# VarmoLed_-_Rev_A1.net
KiCad netlist of a schematic drawn in EAGLE
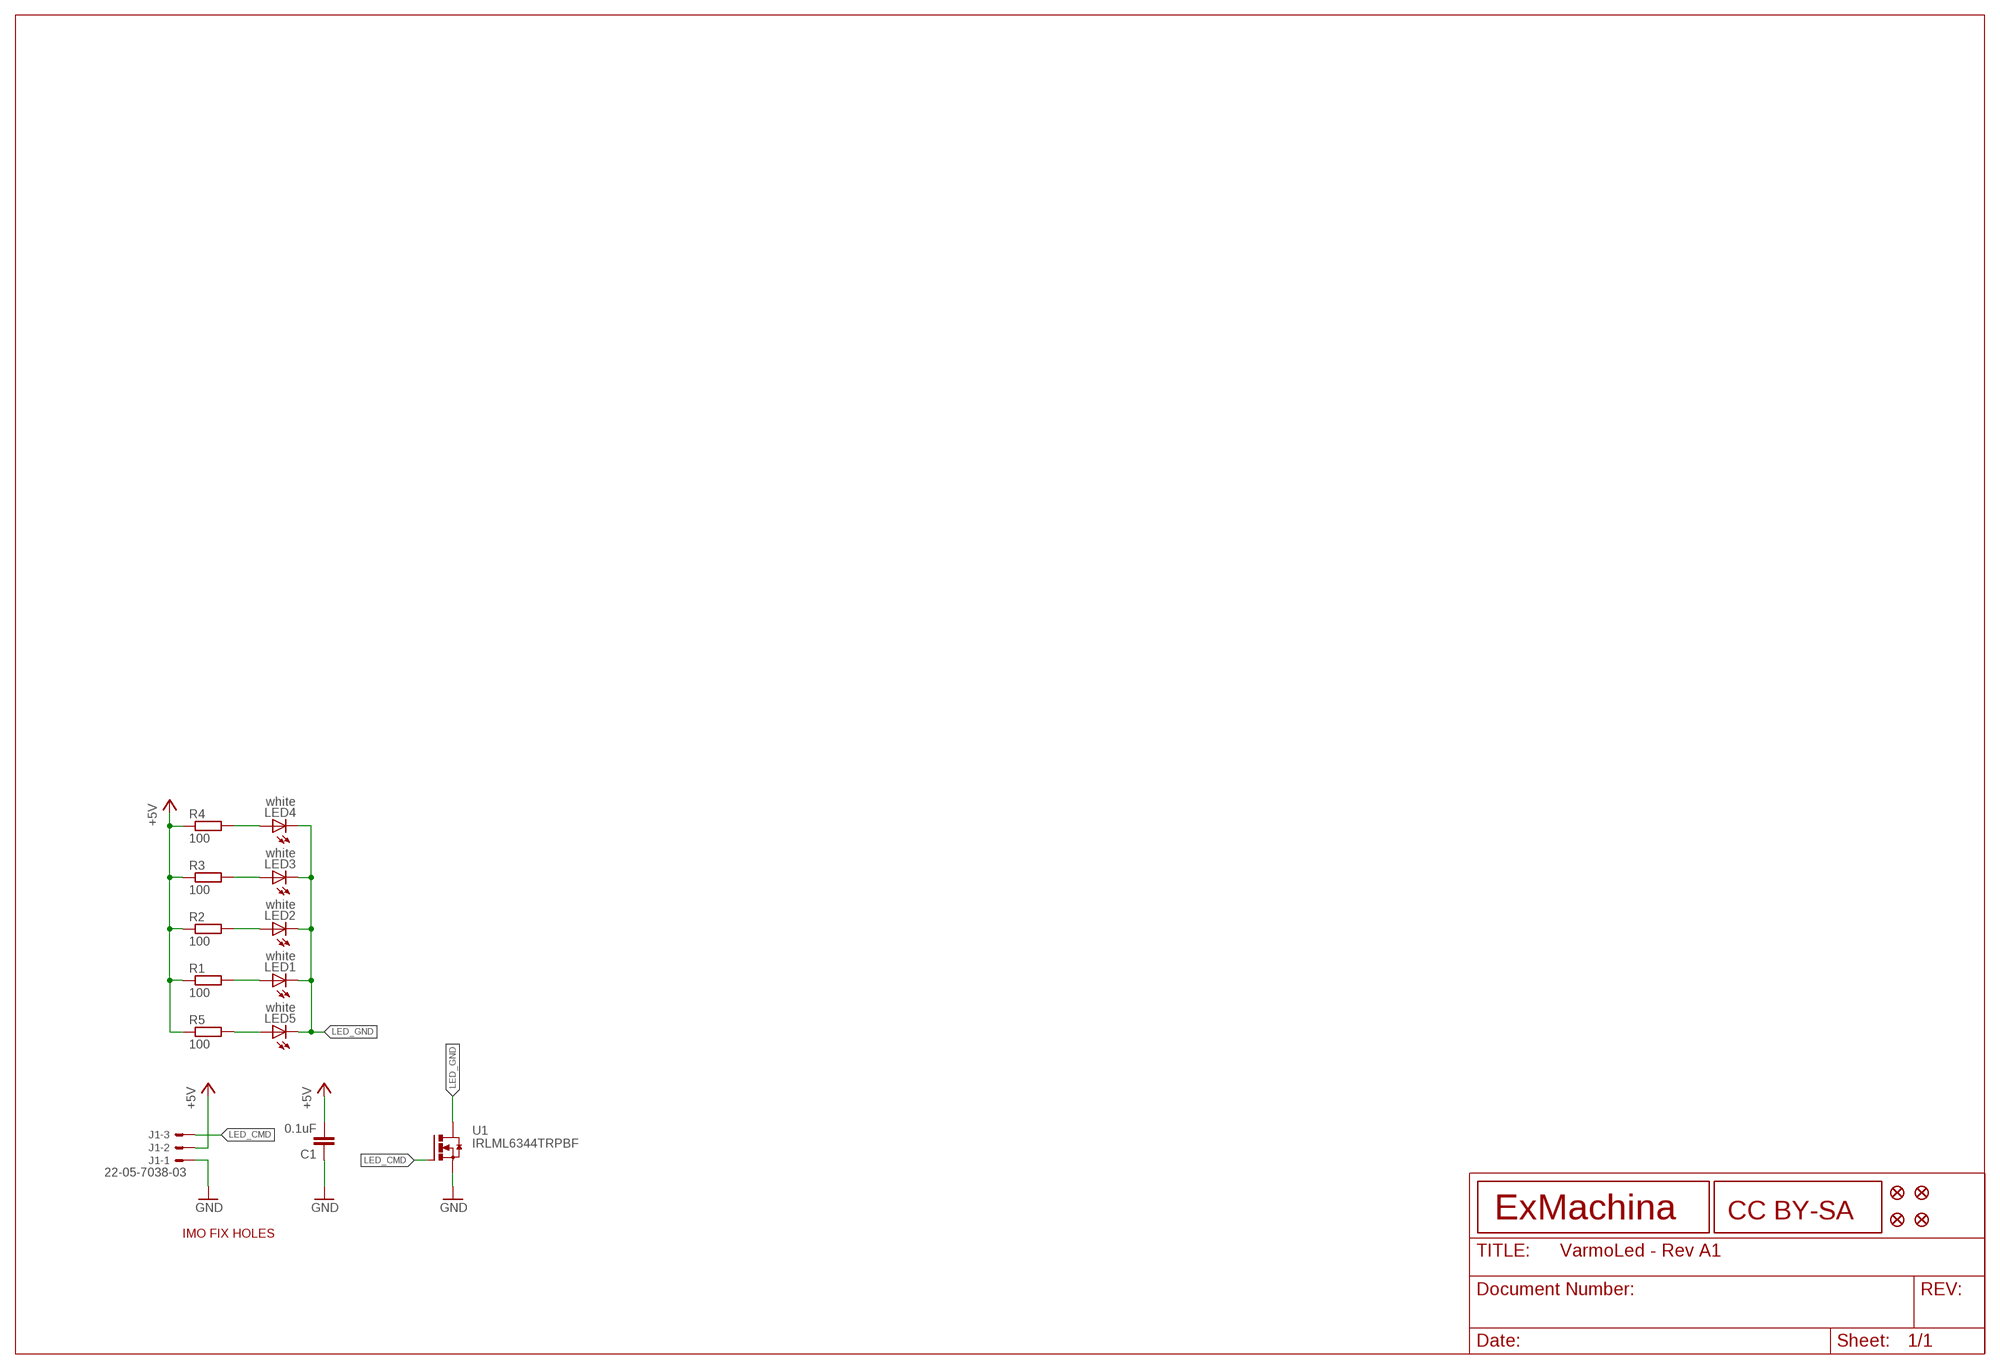
[diagram p0: schematic, sheet 1]

(export (version "E")
  (design (tool "Eeschema 10.0.6"))
  (components
    (comp (ref "C1")
      (value "0.1uF")
      (footprint "eagle-import:C0603")
      (libsource (lib "eagle-import") (part "C-EUC0603"))
    )
    (comp (ref "J1")
      (value "22-05-7038-03")
      (footprint "eagle-import:7395-03")
      (libsource (lib "eagle-import") (part "22-?-0305-7038"))
    )
    (comp (ref "JP1")
      (value "FIDUCIAL1X2")
      (footprint "eagle-import:FIDUCIAL-1X2")
      (libsource (lib "eagle-import") (part "FIDUCIAL1X2"))
    )
    (comp (ref "JP2")
      (value "FIDUCIAL1X2")
      (footprint "eagle-import:FIDUCIAL-1X2")
      (libsource (lib "eagle-import") (part "FIDUCIAL1X2"))
    )
    (comp (ref "JP3")
      (value "FIDUCIAL1X2")
      (footprint "eagle-import:FIDUCIAL-1X2")
      (libsource (lib "eagle-import") (part "FIDUCIAL1X2"))
    )
    (comp (ref "JP4")
      (value "FIDUCIAL1X2")
      (footprint "eagle-import:FIDUCIAL-1X2")
      (libsource (lib "eagle-import") (part "FIDUCIAL1X2"))
    )
    (comp (ref "LED1")
      (value "white")
      (footprint "eagle-import:CHIP-LED0603")
      (libsource (lib "eagle-import") (part "LEDCHIP-LED0603"))
    )
    (comp (ref "LED2")
      (value "white")
      (footprint "eagle-import:CHIP-LED0603")
      (libsource (lib "eagle-import") (part "LEDCHIP-LED0603"))
    )
    (comp (ref "LED3")
      (value "white")
      (footprint "eagle-import:CHIP-LED0603")
      (libsource (lib "eagle-import") (part "LEDCHIP-LED0603"))
    )
    (comp (ref "LED4")
      (value "white")
      (footprint "eagle-import:CHIP-LED0603")
      (libsource (lib "eagle-import") (part "LEDCHIP-LED0603"))
    )
    (comp (ref "LED5")
      (value "white")
      (footprint "eagle-import:CHIP-LED0603")
      (libsource (lib "eagle-import") (part "LEDCHIP-LED0603"))
    )
    (comp (ref "R1")
      (value "100")
      (footprint "eagle-import:R0603")
      (libsource (lib "eagle-import") (part "R-EU_R0603"))
    )
    (comp (ref "R2")
      (value "100")
      (footprint "eagle-import:R0603")
      (libsource (lib "eagle-import") (part "R-EU_R0603"))
    )
    (comp (ref "R3")
      (value "100")
      (footprint "eagle-import:R0603")
      (libsource (lib "eagle-import") (part "R-EU_R0603"))
    )
    (comp (ref "R4")
      (value "100")
      (footprint "eagle-import:R0603")
      (libsource (lib "eagle-import") (part "R-EU_R0603"))
    )
    (comp (ref "R5")
      (value "100")
      (footprint "eagle-import:R0603")
      (libsource (lib "eagle-import") (part "R-EU_R0603"))
    )
    (comp (ref "U$1")
      (value "IMO-FIXHOLES")
      (footprint "eagle-import:IMO-FIXHOLES")
      (libsource (lib "eagle-import") (part "IMO-FIXHOLES"))
    )
    (comp (ref "U$2")
      (value "EXMACHINA-LOGO-NAME")
      (footprint "eagle-import:EXM-LOGO-BASELINE")
      (libsource (lib "eagle-import") (part "EXMACHINA-LOGO-NAME"))
    )
    (comp (ref "U$3")
      (value "CC-BY-SA")
      (footprint "eagle-import:CC-BY-SA")
      (libsource (lib "eagle-import") (part "CC-BY-SA"))
    )
    (comp (ref "U1")
      (value "IRLML6344TRPBF")
      (footprint "eagle-import:SOT95P240X112-3N")
      (libsource (lib "eagle-import") (part "IRLML6344TRPBF"))
    )
  )
  (nets
    (net (code "1") (name "+5V") (class "Default")
      (node (ref "C1") (pin "2") (pinfunction "2_2") (pintype "passive"))
      (node (ref "J1") (pin "2") (pinfunction "S_2") (pintype "passive"))
      (node (ref "R1") (pin "1") (pinfunction "1_1") (pintype "passive"))
      (node (ref "R2") (pin "1") (pinfunction "1_1") (pintype "passive"))
      (node (ref "R3") (pin "1") (pinfunction "1_1") (pintype "passive"))
      (node (ref "R4") (pin "1") (pinfunction "1_1") (pintype "passive"))
      (node (ref "R5") (pin "1") (pinfunction "1_1") (pintype "passive"))
    )
    (net (code "2") (name "GND") (class "Default")
      (node (ref "C1") (pin "1") (pinfunction "1_1") (pintype "passive"))
      (node (ref "J1") (pin "1") (pinfunction "S_1") (pintype "passive"))
      (node (ref "U1") (pin "2") (pinfunction "S_2") (pintype "passive"))
    )
    (net (code "3") (name "LED_CMD") (class "Default")
      (node (ref "J1") (pin "3") (pinfunction "S_3") (pintype "passive"))
      (node (ref "U1") (pin "1") (pinfunction "G_1") (pintype "input"))
    )
    (net (code "4") (name "LED_GND") (class "Default")
      (node (ref "LED1") (pin "C") (pinfunction "C_C") (pintype "passive"))
      (node (ref "LED2") (pin "C") (pinfunction "C_C") (pintype "passive"))
      (node (ref "LED3") (pin "C") (pinfunction "C_C") (pintype "passive"))
      (node (ref "LED4") (pin "C") (pinfunction "C_C") (pintype "passive"))
      (node (ref "LED5") (pin "C") (pinfunction "C_C") (pintype "passive"))
      (node (ref "U1") (pin "3") (pinfunction "D_3") (pintype "output"))
    )
    (net (code "5") (name "Net-(LED1-PadA)") (class "Default")
      (node (ref "LED1") (pin "A") (pinfunction "A_A") (pintype "passive"))
      (node (ref "R1") (pin "2") (pinfunction "2_2") (pintype "passive"))
    )
    (net (code "6") (name "Net-(LED2-PadA)") (class "Default")
      (node (ref "LED2") (pin "A") (pinfunction "A_A") (pintype "passive"))
      (node (ref "R2") (pin "2") (pinfunction "2_2") (pintype "passive"))
    )
    (net (code "7") (name "Net-(LED3-PadA)") (class "Default")
      (node (ref "LED3") (pin "A") (pinfunction "A_A") (pintype "passive"))
      (node (ref "R3") (pin "2") (pinfunction "2_2") (pintype "passive"))
    )
    (net (code "8") (name "Net-(LED4-PadA)") (class "Default")
      (node (ref "LED4") (pin "A") (pinfunction "A_A") (pintype "passive"))
      (node (ref "R4") (pin "2") (pinfunction "2_2") (pintype "passive"))
    )
    (net (code "9") (name "Net-(LED5-PadA)") (class "Default")
      (node (ref "LED5") (pin "A") (pinfunction "A_A") (pintype "passive"))
      (node (ref "R5") (pin "2") (pinfunction "2_2") (pintype "passive"))
    )
  )
)
